# mc33775.net
KiCad netlist of a schematic drawn in Altium Designer
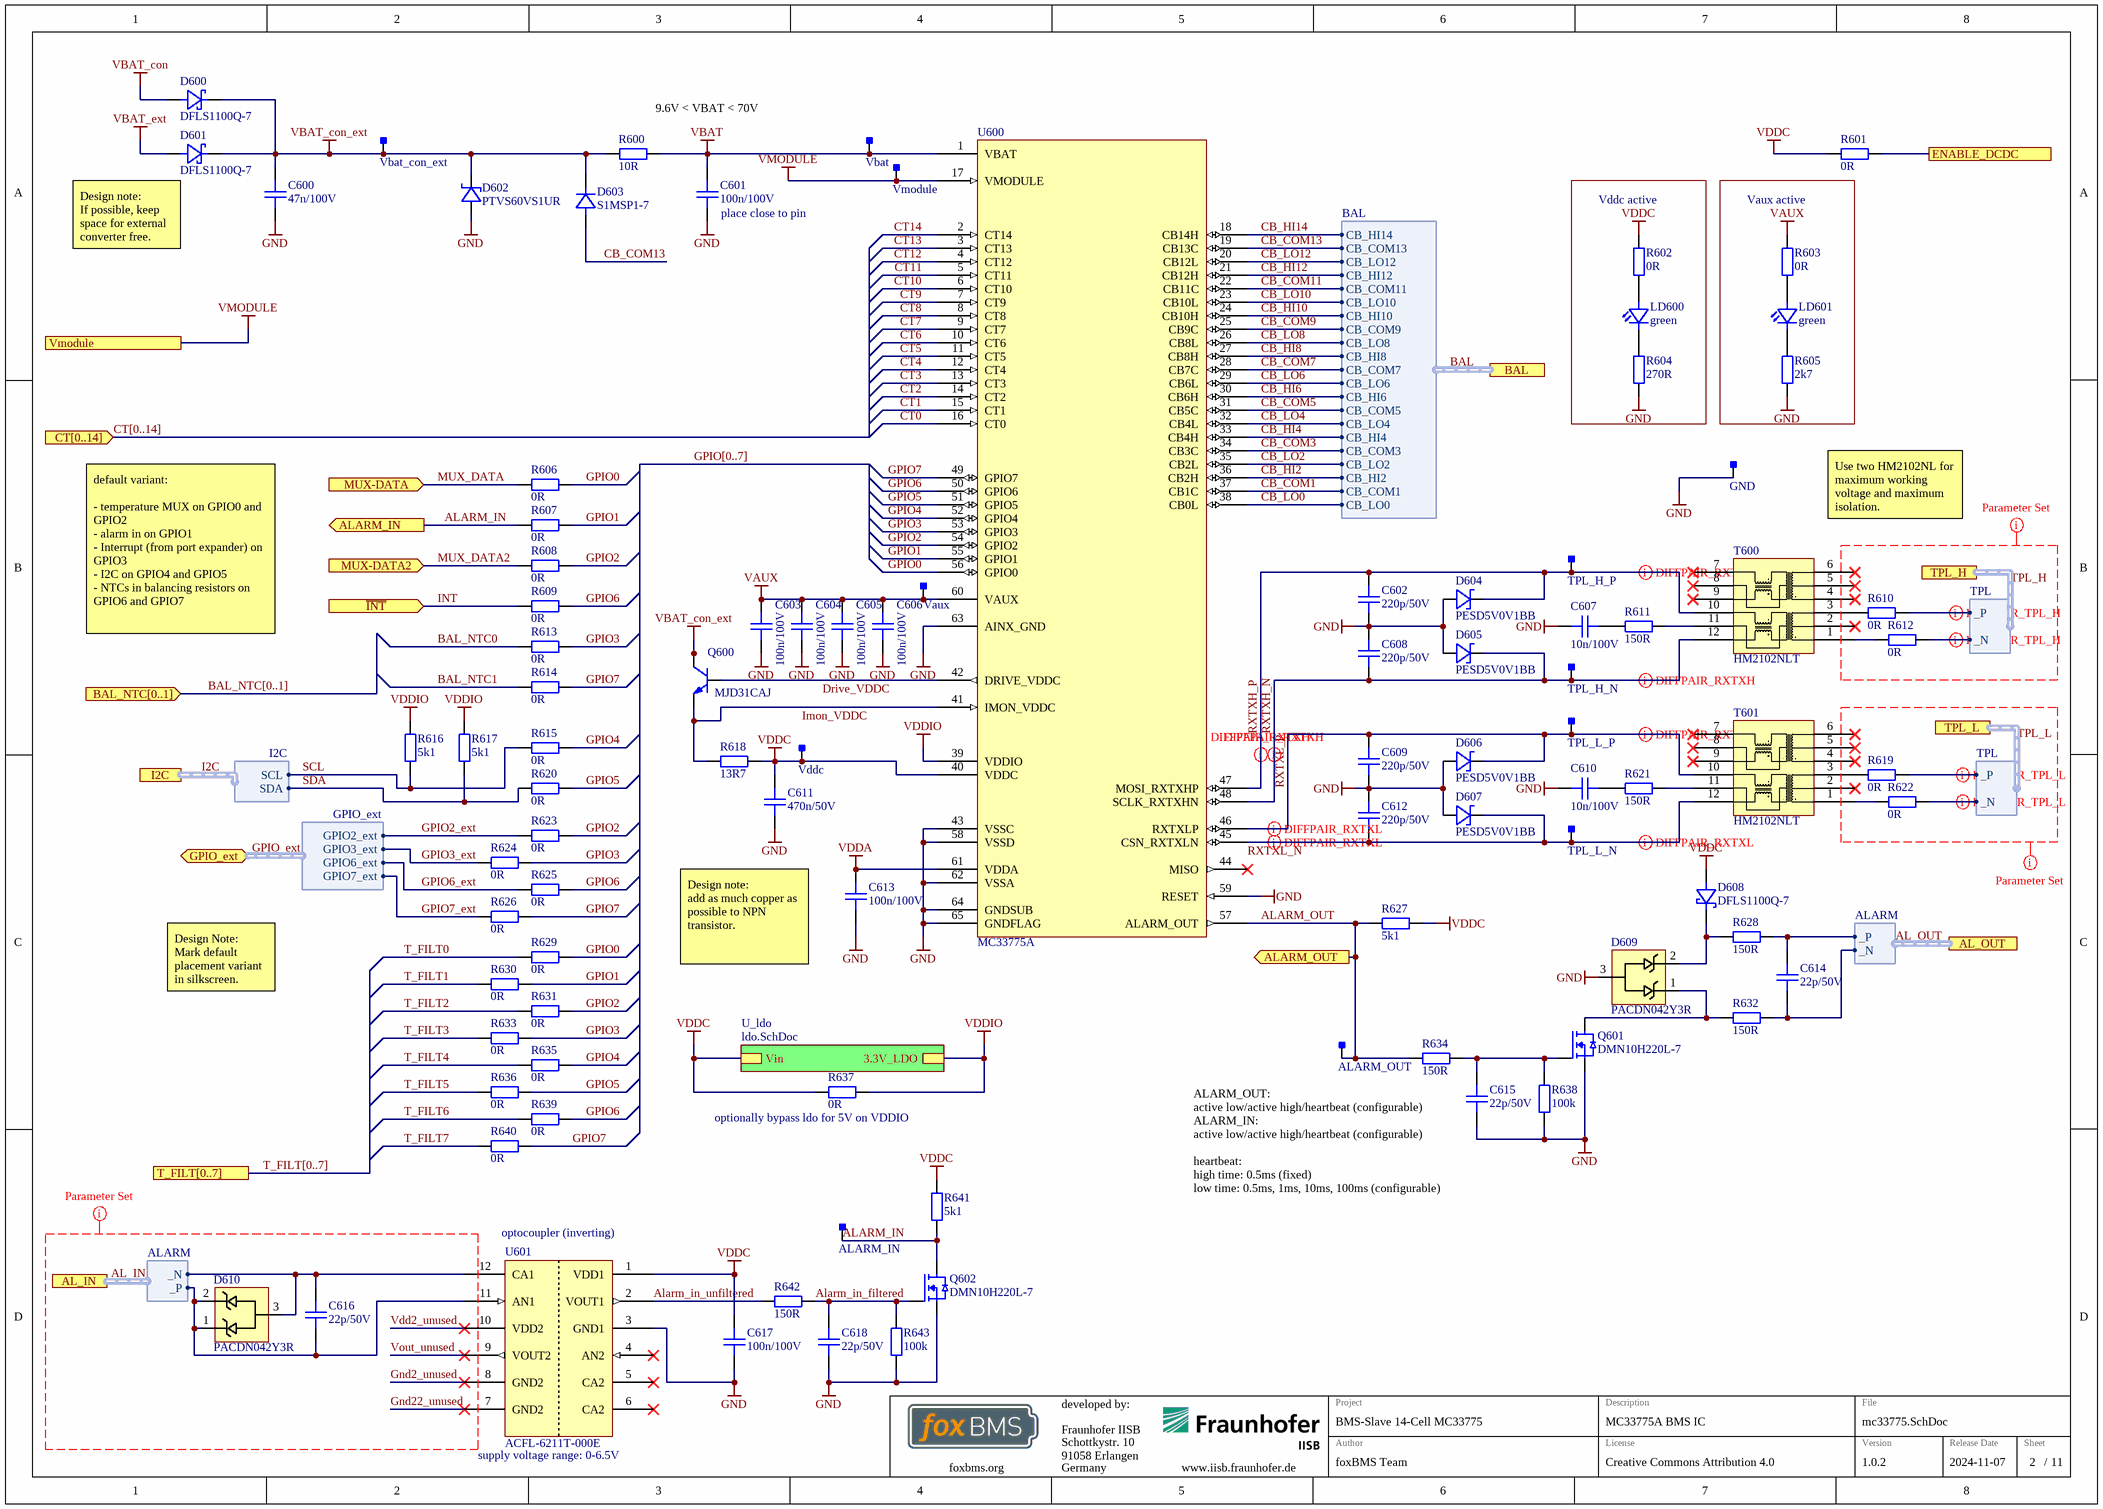
[diagram p0: mc33775.SchDoc]

(export (version "E")
  (design (tool "Eeschema 10.0.6"))
  (components
    (comp (ref "ALARM_IN")
      (value "Testpoint_Square")
      (footprint "Testpoint_S1")
      (description "Testpoint, square")
      (libsource (lib "OE750") (part "Testpoint_Square"))
    )
    (comp (ref "ALARM_OUT")
      (value "Testpoint_Square")
      (footprint "Testpoint_S1")
      (description "Testpoint, square")
      (libsource (lib "OE750") (part "Testpoint_Square"))
    )
    (comp (ref "C600")
      (value "47n/100V")
      (footprint "CAPC1608X08N")
      (description "MLCC")
      (fields (field (name "PART NUMBER") "gen_C_ceramic_47n_100V_X7R_0603"))
      (libsource (lib "OE750") (part "C"))
    )
    (comp (ref "C601")
      (value "100n/100V")
      (footprint "CAPC1608X08N")
      (description "MLCC")
      (fields (field (name "PART NUMBER") "gen_C_ceramic_100n_100V_X7R_0603"))
      (libsource (lib "OE750") (part "C"))
    )
    (comp (ref "C602")
      (value "220p/50V")
      (footprint "CAPC1608X08N")
      (description "MLCC")
      (fields (field (name "PART NUMBER") "gen_C_ceramic_220p_50V_C0G_0603"))
      (libsource (lib "OE750") (part "C"))
    )
    (comp (ref "C603")
      (value "100n/100V")
      (footprint "CAPC1608X08N")
      (description "MLCC")
      (fields (field (name "PART NUMBER") "gen_C_ceramic_100n_100V_X7R_0603"))
      (libsource (lib "OE750") (part "C"))
    )
    (comp (ref "C604")
      (value "100n/100V")
      (footprint "CAPC1608X08N")
      (description "MLCC")
      (fields (field (name "PART NUMBER") "gen_C_ceramic_100n_100V_X7R_0603"))
      (libsource (lib "OE750") (part "C"))
    )
    (comp (ref "C605")
      (value "100n/100V")
      (footprint "CAPC1608X08N")
      (description "MLCC")
      (fields (field (name "PART NUMBER") "gen_C_ceramic_100n_100V_X7R_0603"))
      (libsource (lib "OE750") (part "C"))
    )
    (comp (ref "C606")
      (value "100n/100V")
      (footprint "CAPC1608X08N")
      (description "MLCC")
      (fields (field (name "PART NUMBER") "gen_C_ceramic_100n_100V_X7R_0603"))
      (libsource (lib "OE750") (part "C"))
    )
    (comp (ref "C607")
      (value "10n/100V")
      (footprint "CAPC1608X08N")
      (description "MLCC")
      (fields (field (name "PART NUMBER") "gen_C_ceramic_10n_100V_X7R_0603"))
      (libsource (lib "OE750") (part "C"))
    )
    (comp (ref "C608")
      (value "220p/50V")
      (footprint "CAPC1608X08N")
      (description "MLCC")
      (fields (field (name "PART NUMBER") "gen_C_ceramic_220p_50V_C0G_0603"))
      (libsource (lib "OE750") (part "C"))
    )
    (comp (ref "C609")
      (value "220p/50V")
      (footprint "CAPC1608X08N")
      (description "MLCC")
      (fields (field (name "PART NUMBER") "gen_C_ceramic_220p_50V_C0G_0603"))
      (libsource (lib "OE750") (part "C"))
    )
    (comp (ref "C610")
      (value "10n/100V")
      (footprint "CAPC1608X08N")
      (description "MLCC")
      (fields (field (name "PART NUMBER") "gen_C_ceramic_10n_100V_X7R_0603"))
      (libsource (lib "OE750") (part "C"))
    )
    (comp (ref "C611")
      (value "470n/50V")
      (footprint "CAPC1608X08N")
      (description "MLCC")
      (fields (field (name "PART NUMBER") "gen_C_ceramic_470n_50V_X7R_0603"))
      (libsource (lib "OE750") (part "C"))
    )
    (comp (ref "C612")
      (value "220p/50V")
      (footprint "CAPC1608X08N")
      (description "MLCC")
      (fields (field (name "PART NUMBER") "gen_C_ceramic_220p_50V_C0G_0603"))
      (libsource (lib "OE750") (part "C"))
    )
    (comp (ref "C613")
      (value "100n/100V")
      (footprint "CAPC1608X08N")
      (description "MLCC")
      (fields (field (name "PART NUMBER") "gen_C_ceramic_100n_100V_X7R_0603"))
      (libsource (lib "OE750") (part "C"))
    )
    (comp (ref "C614")
      (value "22p/50V")
      (footprint "CAPC1005X06N")
      (description "MLCC")
      (fields (field (name "PART NUMBER") "gen_C_ceramic_22p_50V_C0G_0402") (field (name "TOLERANCE") "1%"))
      (libsource (lib "OE750") (part "C"))
    )
    (comp (ref "C615")
      (value "22p/50V")
      (footprint "CAPC1005X06N")
      (description "MLCC")
      (fields (field (name "PART NUMBER") "gen_C_ceramic_22p_50V_C0G_0402") (field (name "TOLERANCE") "1%"))
      (libsource (lib "OE750") (part "C"))
    )
    (comp (ref "C616")
      (value "22p/50V")
      (footprint "CAPC1005X06N")
      (description "MLCC")
      (fields (field (name "PART NUMBER") "gen_C_ceramic_22p_50V_C0G_0402") (field (name "TOLERANCE") "1%"))
      (libsource (lib "OE750") (part "C"))
    )
    (comp (ref "C617")
      (value "100n/100V")
      (footprint "CAPC1608X08N")
      (description "MLCC")
      (fields (field (name "PART NUMBER") "gen_C_ceramic_100n_100V_X7R_0603"))
      (libsource (lib "OE750") (part "C"))
    )
    (comp (ref "C618")
      (value "22p/50V")
      (footprint "CAPC1005X06N")
      (description "MLCC")
      (fields (field (name "PART NUMBER") "gen_C_ceramic_22p_50V_C0G_0402") (field (name "TOLERANCE") "1%"))
      (libsource (lib "OE750") (part "C"))
    )
    (comp (ref "D600")
      (value "DFLS1100Q-7")
      (footprint "PowerDI123")
      (description "Schottky Diode")
      (fields (field (name "MANUFACTURER") "Diodes Inc."))
      (libsource (lib "OE750") (part "D_Schottky"))
    )
    (comp (ref "D601")
      (value "DFLS1100Q-7")
      (footprint "PowerDI123")
      (description "Schottky Diode")
      (fields (field (name "MANUFACTURER") "Diodes Inc."))
      (libsource (lib "OE750") (part "D_Schottky"))
    )
    (comp (ref "D602")
      (value "PTVS60VS1UR")
      (footprint "NEXPERIA_PTVSxS1UR")
      (description "400W Transient Voltage Suppressor")
      (fields (field (name "MANUFACTURER") "Nexperia"))
      (libsource (lib "OE750") (part "D_TVS"))
    )
    (comp (ref "D603")
      (value "S1MSP1-7")
      (footprint "S1MSP1")
      (description "1.0A surface mount glass passivated rectifier")
      (fields (field (name "MANUFACTURER") "Diodes Inc."))
      (libsource (lib "OE750") (part "D"))
    )
    (comp (ref "D604")
      (value "PESD5V0V1BB")
      (footprint "SOD523_PESD_NEXPERIA")
      (description "Very low capacitance bidirectional ESD protection diode")
      (fields (field (name "MANUFACTURER") "Nexperia"))
      (libsource (lib "OE750") (part "D_TVS"))
    )
    (comp (ref "D605")
      (value "PESD5V0V1BB")
      (footprint "SOD523_PESD_NEXPERIA")
      (description "Very low capacitance bidirectional ESD protection diode")
      (fields (field (name "MANUFACTURER") "Nexperia"))
      (libsource (lib "OE750") (part "D_TVS"))
    )
    (comp (ref "D606")
      (value "PESD5V0V1BB")
      (footprint "SOD523_PESD_NEXPERIA")
      (description "Very low capacitance bidirectional ESD protection diode")
      (fields (field (name "MANUFACTURER") "Nexperia"))
      (libsource (lib "OE750") (part "D_TVS"))
    )
    (comp (ref "D607")
      (value "PESD5V0V1BB")
      (footprint "SOD523_PESD_NEXPERIA")
      (description "Very low capacitance bidirectional ESD protection diode")
      (fields (field (name "MANUFACTURER") "Nexperia"))
      (libsource (lib "OE750") (part "D_TVS"))
    )
    (comp (ref "D608")
      (value "DFLS1100Q-7")
      (footprint "PowerDI123")
      (description "Schottky Diode")
      (fields (field (name "MANUFACTURER") "Diodes Inc."))
      (libsource (lib "OE750") (part "D_Schottky"))
    )
    (comp (ref "D609")
      (value "PACDN042Y3R")
      (footprint "ON-SEMI-SOT-23-3-CASE-318-08")
      (description "ESD-Schutzbaustein")
      (fields (field (name "MANUFACTURER") "ON Semiconductor"))
      (libsource (lib "") (part "PACDN042_1"))
    )
    (comp (ref "D610")
      (value "PACDN042Y3R")
      (footprint "ON-SEMI-SOT-23-3-CASE-318-08")
      (description "ESD-Schutzbaustein")
      (fields (field (name "MANUFACTURER") "ON Semiconductor"))
      (libsource (lib "OE750") (part "PACDN042"))
    )
    (comp (ref "GND")
      (value "Testpoint_Square")
      (footprint "Testpoint_S1")
      (description "Testpoint, square")
      (libsource (lib "OE750") (part "Testpoint_Square"))
    )
    (comp (ref "LD600")
      (value "green")
      (footprint "LEDC1608X07N")
      (description "TLMG1100-GS08")
      (fields (field (name "PART NUMBER") "LED_0603_green_AECQ") (field (name "MANUFACTURER") "Vishay"))
      (libsource (lib "OE750") (part "D_LED"))
    )
    (comp (ref "LD601")
      (value "green")
      (footprint "LEDC1608X07N")
      (description "TLMG1100-GS08")
      (fields (field (name "PART NUMBER") "LED_0603_green_AECQ") (field (name "MANUFACTURER") "Vishay"))
      (libsource (lib "OE750") (part "D_LED"))
    )
    (comp (ref "Q600")
      (value "MJD31CAJ")
      (footprint "NEXPERIA_DPAK_SOT428C")
      (description "100V, 3A NPN high power bipolar transistor")
      (fields (field (name "MANUFACTURER") "Nexperia"))
      (libsource (lib "OE750") (part "NPN_4_PIN"))
    )
    (comp (ref "Q601")
      (value "DMN10H220L-7")
      (footprint "SOT95P237X110-3N")
      (description "MOSFET-Transistor, n-Kanal, 1.6 A, 100 V, 0.250 ohm")
      (fields (field (name "MANUFACTURER") "Diodes"))
      (libsource (lib "OE750") (part "NMOS"))
    )
    (comp (ref "Q602")
      (value "DMN10H220L-7")
      (footprint "SOT95P237X110-3N")
      (description "MOSFET-Transistor, n-Kanal, 1.6 A, 100 V, 0.250 ohm")
      (fields (field (name "MANUFACTURER") "Diodes"))
      (libsource (lib "OE750") (part "NMOS"))
    )
    (comp (ref "R600")
      (value "10R")
      (footprint "RESC2012X05N")
      (description "SMD Resistor 10R 0805")
      (fields (field (name "PART NUMBER") "gen_R_10R_0805") (field (name "TOLERANCE") "1%"))
      (libsource (lib "OE750") (part "R"))
    )
    (comp (ref "R601")
      (value "0R")
      (footprint "RESC1608X05N")
      (description "SMD Resistor 0R 0603")
      (fields (field (name "PART NUMBER") "gen_R_0R_0603") (field (name "POWER") "0.1W"))
      (libsource (lib "OE750") (part "R"))
    )
    (comp (ref "R602")
      (value "0R")
      (footprint "RESC1608X05N")
      (description "SMD Resistor 0R 0603")
      (fields (field (name "PART NUMBER") "gen_R_0R_0603") (field (name "POWER") "0.1W"))
      (libsource (lib "OE750") (part "R"))
    )
    (comp (ref "R603")
      (value "0R")
      (footprint "RESC1608X05N")
      (description "SMD Resistor 0R 0603")
      (fields (field (name "PART NUMBER") "gen_R_0R_0603") (field (name "POWER") "0.1W"))
      (libsource (lib "OE750") (part "R"))
    )
    (comp (ref "R604")
      (value "270R")
      (footprint "RESC1608X05N")
      (description "SMD Resistor 270R 0603")
      (fields (field (name "PART NUMBER") "gen_R_270R_0603") (field (name "TOLERANCE") "1%"))
      (libsource (lib "OE750") (part "R"))
    )
    (comp (ref "R605")
      (value "2k7")
      (footprint "RESC1608X05N")
      (description "SMD Resistor 2k7 0603")
      (fields (field (name "PART NUMBER") "gen_R_2k7_0603") (field (name "TOLERANCE") "1%"))
      (libsource (lib "OE750") (part "R"))
    )
    (comp (ref "R606")
      (value "0R")
      (footprint "RESC1608X05N")
      (description "SMD Resistor 0R 0603")
      (fields (field (name "PART NUMBER") "gen_R_0R_0603") (field (name "POWER") "0.1W"))
      (libsource (lib "OE750") (part "R"))
    )
    (comp (ref "R607")
      (value "0R")
      (footprint "RESC1608X05N")
      (description "SMD Resistor 0R 0603")
      (fields (field (name "PART NUMBER") "gen_R_0R_0603") (field (name "POWER") "0.1W"))
      (libsource (lib "OE750") (part "R"))
    )
    (comp (ref "R608")
      (value "0R")
      (footprint "RESC1608X05N")
      (description "SMD Resistor 0R 0603")
      (fields (field (name "PART NUMBER") "gen_R_0R_0603") (field (name "POWER") "0.1W"))
      (libsource (lib "OE750") (part "R"))
    )
    (comp (ref "R609")
      (value "0R")
      (footprint "RESC1608X05N")
      (description "SMD Resistor 0R 0603")
      (fields (field (name "PART NUMBER") "gen_R_0R_0603") (field (name "POWER") "0.1W"))
      (libsource (lib "OE750") (part "R"))
    )
    (comp (ref "R610")
      (value "0R")
      (footprint "RESC1608X05N")
      (description "SMD Resistor 0R 0603")
      (fields (field (name "PART NUMBER") "gen_R_0R_0603") (field (name "POWER") "0.1W"))
      (libsource (lib "OE750") (part "R"))
    )
    (comp (ref "R611")
      (value "150R")
      (footprint "RESC1608X05N")
      (description "SMD Resistor 150R 0603")
      (fields (field (name "PART NUMBER") "gen_R_150R_0603") (field (name "TOLERANCE") "1%"))
      (libsource (lib "OE750") (part "R"))
    )
    (comp (ref "R612")
      (value "0R")
      (footprint "RESC1608X05N")
      (description "SMD Resistor 0R 0603")
      (fields (field (name "PART NUMBER") "gen_R_0R_0603") (field (name "POWER") "0.1W"))
      (libsource (lib "OE750") (part "R"))
    )
    (comp (ref "R613")
      (value "0R")
      (footprint "RESC1608X05N")
      (description "SMD Resistor 0R 0603")
      (fields (field (name "PART NUMBER") "gen_R_0R_0603") (field (name "POWER") "0.1W"))
      (libsource (lib "OE750") (part "R"))
    )
    (comp (ref "R614")
      (value "0R")
      (footprint "RESC1608X05N")
      (description "SMD Resistor 0R 0603")
      (fields (field (name "PART NUMBER") "gen_R_0R_0603") (field (name "POWER") "0.1W"))
      (libsource (lib "OE750") (part "R"))
    )
    (comp (ref "R615")
      (value "0R")
      (footprint "RESC1608X05N")
      (description "SMD Resistor 0R 0603")
      (fields (field (name "PART NUMBER") "gen_R_0R_0603") (field (name "POWER") "0.1W"))
      (libsource (lib "OE750") (part "R"))
    )
    (comp (ref "R616")
      (value "5k1")
      (footprint "RESC1608X05N")
      (description "SMD Resistor 5k1 0603")
      (fields (field (name "PART NUMBER") "gen_R_5k1_0603") (field (name "TOLERANCE") "5%"))
      (libsource (lib "OE750") (part "R"))
    )
    (comp (ref "R617")
      (value "5k1")
      (footprint "RESC1608X05N")
      (description "SMD Resistor 5k1 0603")
      (fields (field (name "PART NUMBER") "gen_R_5k1_0603") (field (name "TOLERANCE") "5%"))
      (libsource (lib "OE750") (part "R"))
    )
    (comp (ref "R618")
      (value "13R7")
      (footprint "RESC1608X05N")
      (description "SMD Resistor 13R7 0603")
      (fields (field (name "PART NUMBER") "gen_R_13R7_0603") (field (name "TOLERANCE") "1%"))
      (libsource (lib "OE750") (part "R"))
    )
    (comp (ref "R619")
      (value "0R")
      (footprint "RESC1608X05N")
      (description "SMD Resistor 0R 0603")
      (fields (field (name "PART NUMBER") "gen_R_0R_0603") (field (name "POWER") "0.1W"))
      (libsource (lib "OE750") (part "R"))
    )
    (comp (ref "R620")
      (value "0R")
      (footprint "RESC1608X05N")
      (description "SMD Resistor 0R 0603")
      (fields (field (name "PART NUMBER") "gen_R_0R_0603") (field (name "POWER") "0.1W"))
      (libsource (lib "OE750") (part "R"))
    )
    (comp (ref "R621")
      (value "150R")
      (footprint "RESC1608X05N")
      (description "SMD Resistor 150R 0603")
      (fields (field (name "PART NUMBER") "gen_R_150R_0603") (field (name "TOLERANCE") "1%"))
      (libsource (lib "OE750") (part "R"))
    )
    (comp (ref "R622")
      (value "0R")
      (footprint "RESC1608X05N")
      (description "SMD Resistor 0R 0603")
      (fields (field (name "PART NUMBER") "gen_R_0R_0603") (field (name "POWER") "0.1W"))
      (libsource (lib "OE750") (part "R"))
    )
    (comp (ref "R623")
      (value "0R")
      (footprint "RESC1608X05N")
      (description "SMD Resistor 0R 0603")
      (fields (field (name "PART NUMBER") "gen_R_0R_0603") (field (name "POWER") "0.1W"))
      (libsource (lib "OE750") (part "R"))
    )
    (comp (ref "R624")
      (value "0R")
      (footprint "RESC1608X05N")
      (description "SMD Resistor 0R 0603")
      (fields (field (name "PART NUMBER") "gen_R_0R_0603") (field (name "POWER") "0.1W"))
      (libsource (lib "OE750") (part "R"))
    )
    (comp (ref "R625")
      (value "0R")
      (footprint "RESC1608X05N")
      (description "SMD Resistor 0R 0603")
      (fields (field (name "PART NUMBER") "gen_R_0R_0603") (field (name "POWER") "0.1W"))
      (libsource (lib "OE750") (part "R"))
    )
    (comp (ref "R626")
      (value "0R")
      (footprint "RESC1608X05N")
      (description "SMD Resistor 0R 0603")
      (fields (field (name "PART NUMBER") "gen_R_0R_0603") (field (name "POWER") "0.1W"))
      (libsource (lib "OE750") (part "R"))
    )
    (comp (ref "R627")
      (value "5k1")
      (footprint "RESC1608X05N")
      (description "SMD Resistor 5k1 0603")
      (fields (field (name "PART NUMBER") "gen_R_5k1_0603") (field (name "TOLERANCE") "5%"))
      (libsource (lib "OE750") (part "R"))
    )
    (comp (ref "R628")
      (value "150R")
      (footprint "RESC1608X05N")
      (description "SMD Resistor 150R 0603")
      (fields (field (name "PART NUMBER") "gen_R_150R_0603") (field (name "TOLERANCE") "1%"))
      (libsource (lib "OE750") (part "R"))
    )
    (comp (ref "R629")
      (value "0R")
      (footprint "RESC1608X05N")
      (description "SMD Resistor 0R 0603")
      (fields (field (name "PART NUMBER") "gen_R_0R_0603") (field (name "POWER") "0.1W"))
      (libsource (lib "OE750") (part "R"))
    )
    (comp (ref "R630")
      (value "0R")
      (footprint "RESC1608X05N")
      (description "SMD Resistor 0R 0603")
      (fields (field (name "PART NUMBER") "gen_R_0R_0603") (field (name "POWER") "0.1W"))
      (libsource (lib "OE750") (part "R"))
    )
    (comp (ref "R631")
      (value "0R")
      (footprint "RESC1608X05N")
      (description "SMD Resistor 0R 0603")
      (fields (field (name "PART NUMBER") "gen_R_0R_0603") (field (name "POWER") "0.1W"))
      (libsource (lib "OE750") (part "R"))
    )
    (comp (ref "R632")
      (value "150R")
      (footprint "RESC1608X05N")
      (description "SMD Resistor 150R 0603")
      (fields (field (name "PART NUMBER") "gen_R_150R_0603") (field (name "TOLERANCE") "1%"))
      (libsource (lib "OE750") (part "R"))
    )
    (comp (ref "R633")
      (value "0R")
      (footprint "RESC1608X05N")
      (description "SMD Resistor 0R 0603")
      (fields (field (name "PART NUMBER") "gen_R_0R_0603") (field (name "POWER") "0.1W"))
      (libsource (lib "OE750") (part "R"))
    )
    (comp (ref "R634")
      (value "150R")
      (footprint "RESC1608X05N")
      (description "SMD Resistor 150R 0603")
      (fields (field (name "PART NUMBER") "gen_R_150R_0603") (field (name "TOLERANCE") "1%"))
      (libsource (lib "OE750") (part "R"))
    )
    (comp (ref "R635")
      (value "0R")
      (footprint "RESC1608X05N")
      (description "SMD Resistor 0R 0603")
      (fields (field (name "PART NUMBER") "gen_R_0R_0603") (field (name "POWER") "0.1W"))
      (libsource (lib "OE750") (part "R"))
    )
    (comp (ref "R636")
      (value "0R")
      (footprint "RESC1608X05N")
      (description "SMD Resistor 0R 0603")
      (fields (field (name "PART NUMBER") "gen_R_0R_0603") (field (name "POWER") "0.1W"))
      (libsource (lib "OE750") (part "R"))
    )
    (comp (ref "R637")
      (value "0R")
      (footprint "RESC1608X05N")
      (description "SMD Resistor 0R 0603")
      (fields (field (name "PART NUMBER") "gen_R_0R_0603") (field (name "POWER") "0.1W"))
      (libsource (lib "OE750") (part "R"))
    )
    (comp (ref "R638")
      (value "100k")
      (footprint "RESC1608X05N")
      (description "SMD Resistor 100k 0603")
      (fields (field (name "PART NUMBER") "gen_R_100k_0603") (field (name "TOLERANCE") "1%"))
      (libsource (lib "OE750") (part "R"))
    )
    (comp (ref "R639")
      (value "0R")
      (footprint "RESC1608X05N")
      (description "SMD Resistor 0R 0603")
      (fields (field (name "PART NUMBER") "gen_R_0R_0603") (field (name "POWER") "0.1W"))
      (libsource (lib "OE750") (part "R"))
    )
    (comp (ref "R640")
      (value "0R")
      (footprint "RESC1608X05N")
      (description "SMD Resistor 0R 0603")
      (fields (field (name "PART NUMBER") "gen_R_0R_0603") (field (name "POWER") "0.1W"))
      (libsource (lib "OE750") (part "R"))
    )
    (comp (ref "R641")
      (value "5k1")
      (footprint "RESC1608X05N")
      (description "SMD Resistor 5k1 0603")
      (fields (field (name "PART NUMBER") "gen_R_5k1_0603") (field (name "TOLERANCE") "5%"))
      (libsource (lib "OE750") (part "R"))
    )
    (comp (ref "R642")
      (value "150R")
      (footprint "RESC1608X05N")
      (description "SMD Resistor 150R 0603")
      (fields (field (name "PART NUMBER") "gen_R_150R_0603") (field (name "TOLERANCE") "1%"))
      (libsource (lib "OE750") (part "R"))
    )
    (comp (ref "R643")
      (value "100k")
      (footprint "RESC1608X05N")
      (description "SMD Resistor 100k 0603")
      (fields (field (name "PART NUMBER") "gen_R_100k_0603") (field (name "TOLERANCE") "1%"))
      (libsource (lib "OE750") (part "R"))
    )
    (comp (ref "T600")
      (value "HM2102NLT")
      (footprint "HM2102NL")
      (description "Pulse HM2102NLT BMS Transformer")
      (fields (field (name "MANUFACTURER") "Pulse"))
      (libsource (lib "OE750") (part "HM2102NL"))
    )
    (comp (ref "T601")
      (value "HM2102NLT")
      (footprint "HM2102NL")
      (description "Pulse HM2102NLT BMS Transformer")
      (fields (field (name "MANUFACTURER") "Pulse"))
      (libsource (lib "OE750") (part "HM2102NL"))
    )
    (comp (ref "TPL_H_N")
      (value "Testpoint_Square")
      (footprint "Testpoint_S1")
      (description "Testpoint, square")
      (libsource (lib "OE750") (part "Testpoint_Square"))
    )
    (comp (ref "TPL_H_P")
      (value "Testpoint_Square")
      (footprint "Testpoint_S1")
      (description "Testpoint, square")
      (libsource (lib "OE750") (part "Testpoint_Square"))
    )
    (comp (ref "TPL_L_N")
      (value "Testpoint_Square")
      (footprint "Testpoint_S1")
      (description "Testpoint, square")
      (libsource (lib "OE750") (part "Testpoint_Square"))
    )
    (comp (ref "TPL_L_P")
      (value "Testpoint_Square")
      (footprint "Testpoint_S1")
      (description "Testpoint, square")
      (libsource (lib "OE750") (part "Testpoint_Square"))
    )
    (comp (ref "U600")
      (value "MC33775A")
      (footprint "NXP_SOT1510-2")
      (description "14 Cells Battery Cell Controller IC")
      (fields (field (name "MANUFACTURER") "NXP"))
      (libsource (lib "OE750") (part "MC33775"))
    )
    (comp (ref "U601")
      (value "ACFL-6211T-000E")
      (footprint "Broadcom_ACFL-6211T")
      (description "15MBd Dual-channel Bi-directional Optocoupler")
      (fields (field (name "MANUFACTURER") "Broadcom"))
      (libsource (lib "OE750") (part "ACFL-6211T"))
    )
    (comp (ref "Vaux")
      (value "Testpoint_Square")
      (footprint "Testpoint_S1")
      (description "Testpoint, square")
      (libsource (lib "OE750") (part "Testpoint_Square"))
    )
    (comp (ref "Vbat")
      (value "Testpoint_Square")
      (footprint "Testpoint_S1")
      (description "Testpoint, square")
      (libsource (lib "OE750") (part "Testpoint_Square"))
    )
    (comp (ref "Vbat_con_ext")
      (value "Testpoint_Square")
      (footprint "Testpoint_S1")
      (description "Testpoint, square")
      (libsource (lib "OE750") (part "Testpoint_Square"))
    )
    (comp (ref "Vddc")
      (value "Testpoint_Square")
      (footprint "Testpoint_S1")
      (description "Testpoint, square")
      (libsource (lib "OE750") (part "Testpoint_Square"))
    )
    (comp (ref "Vmodule")
      (value "Testpoint_Square")
      (footprint "Testpoint_S1")
      (description "Testpoint, square")
      (libsource (lib "OE750") (part "Testpoint_Square"))
    )
  )
  (nets
    (net (code "8") (name "/ALARM_IN") (class "Default")
      (node (ref "ALARM_IN") (pin "1") (pinfunction "1_1") (pintype "passive"))
      (node (ref "Q602") (pin "D") (pinfunction "D_D") (pintype "passive"))
      (node (ref "R607") (pin "1") (pinfunction "1_1") (pintype "passive"))
      (node (ref "R641") (pin "2") (pinfunction "2_2") (pintype "passive"))
    )
    (net (code "9") (name "/ALARM_OUT") (class "Default")
      (node (ref "ALARM_OUT") (pin "1") (pinfunction "1_1") (pintype "passive"))
      (node (ref "R627") (pin "2") (pinfunction "2_2") (pintype "passive"))
      (node (ref "R634") (pin "1") (pinfunction "1_1") (pintype "passive"))
      (node (ref "U600") (pin "57") (pinfunction "ALARM_OUT_57") (pintype "output"))
    )
    (net (code "12") (name "/Alarm_in_filtered") (class "Default")
      (node (ref "C618") (pin "2") (pinfunction "2_2") (pintype "passive"))
      (node (ref "Q602") (pin "G") (pinfunction "G_G") (pintype "passive"))
      (node (ref "R642") (pin "2") (pinfunction "2_2") (pintype "passive"))
      (node (ref "R643") (pin "1") (pinfunction "1_1") (pintype "passive"))
    )
    (net (code "13") (name "/Alarm_in_unfiltered") (class "Default")
      (node (ref "R642") (pin "1") (pinfunction "1_1") (pintype "passive"))
      (node (ref "U601") (pin "2") (pinfunction "VOUT1_2") (pintype "output"))
    )
    (net (code "14") (name "/BAL_NTC0") (class "Default")
      (node (ref "R613") (pin "1") (pinfunction "1_1") (pintype "passive"))
    )
    (net (code "15") (name "/BAL_NTC1") (class "Default")
      (node (ref "R614") (pin "1") (pinfunction "1_1") (pintype "passive"))
    )
    (net (code "18") (name "/CB_COM1") (class "Default")
      (node (ref "U600") (pin "37") (pinfunction "CB1C_37") (pintype "bidirectional"))
    )
    (net (code "19") (name "/CB_COM3") (class "Default")
      (node (ref "U600") (pin "34") (pinfunction "CB3C_34") (pintype "bidirectional"))
    )
    (net (code "20") (name "/CB_COM5") (class "Default")
      (node (ref "U600") (pin "31") (pinfunction "CB5C_31") (pintype "bidirectional"))
    )
    (net (code "21") (name "/CB_COM7") (class "Default")
      (node (ref "U600") (pin "28") (pinfunction "CB7C_28") (pintype "bidirectional"))
    )
    (net (code "22") (name "/CB_COM9") (class "Default")
      (node (ref "U600") (pin "25") (pinfunction "CB9C_25") (pintype "bidirectional"))
    )
    (net (code "23") (name "/CB_COM11") (class "Default")
      (node (ref "U600") (pin "22") (pinfunction "CB11C_22") (pintype "bidirectional"))
    )
    (net (code "24") (name "/CB_COM13") (class "Default")
      (node (ref "D603") (pin "2") (pinfunction "A_2") (pintype "passive"))
      (node (ref "U600") (pin "19") (pinfunction "CB13C_19") (pintype "bidirectional"))
    )
    (net (code "25") (name "/CB_HI2") (class "Default")
      (node (ref "U600") (pin "36") (pinfunction "CB2H_36") (pintype "bidirectional"))
    )
    (net (code "26") (name "/CB_HI4") (class "Default")
      (node (ref "U600") (pin "33") (pinfunction "CB4H_33") (pintype "bidirectional"))
    )
    (net (code "27") (name "/CB_HI6") (class "Default")
      (node (ref "U600") (pin "30") (pinfunction "CB6H_30") (pintype "bidirectional"))
    )
    (net (code "28") (name "/CB_HI8") (class "Default")
      (node (ref "U600") (pin "27") (pinfunction "CB8H_27") (pintype "bidirectional"))
    )
    (net (code "29") (name "/CB_HI10") (class "Default")
      (node (ref "U600") (pin "24") (pinfunction "CB10H_24") (pintype "bidirectional"))
    )
    (net (code "30") (name "/CB_HI12") (class "Default")
      (node (ref "U600") (pin "21") (pinfunction "CB12H_21") (pintype "bidirectional"))
    )
    (net (code "31") (name "/CB_HI14") (class "Default")
      (node (ref "U600") (pin "18") (pinfunction "CB14H_18") (pintype "bidirectional"))
    )
    (net (code "32") (name "/CB_LO0") (class "Default")
      (node (ref "U600") (pin "38") (pinfunction "CB0L_38") (pintype "bidirectional"))
    )
    (net (code "33") (name "/CB_LO2") (class "Default")
      (node (ref "U600") (pin "35") (pinfunction "CB2L_35") (pintype "bidirectional"))
    )
    (net (code "34") (name "/CB_LO4") (class "Default")
      (node (ref "U600") (pin "32") (pinfunction "CB4L_32") (pintype "bidirectional"))
    )
    (net (code "35") (name "/CB_LO6") (class "Default")
      (node (ref "U600") (pin "29") (pinfunction "CB6L_29") (pintype "bidirectional"))
    )
    (net (code "36") (name "/CB_LO8") (class "Default")
      (node (ref "U600") (pin "26") (pinfunction "CB8L_26") (pintype "bidirectional"))
    )
    (net (code "37") (name "/CB_LO10") (class "Default")
      (node (ref "U600") (pin "23") (pinfunction "CB10L_23") (pintype "bidirectional"))
    )
    (net (code "38") (name "/CB_LO12") (class "Default")
      (node (ref "U600") (pin "20") (pinfunction "CB12L_20") (pintype "bidirectional"))
    )
    (net (code "39") (name "/CT0") (class "Default")
      (node (ref "U600") (pin "16") (pinfunction "CT0_16") (pintype "input"))
    )
    (net (code "40") (name "/CT1") (class "Default")
      (node (ref "U600") (pin "15") (pinfunction "CT1_15") (pintype "input"))
    )
    (net (code "41") (name "/CT2") (class "Default")
      (node (ref "U600") (pin "14") (pinfunction "CT2_14") (pintype "input"))
    )
    (net (code "42") (name "/CT3") (class "Default")
      (node (ref "U600") (pin "13") (pinfunction "CT3_13") (pintype "input"))
    )
    (net (code "43") (name "/CT4") (class "Default")
      (node (ref "U600") (pin "12") (pinfunction "CT4_12") (pintype "input"))
    )
    (net (code "44") (name "/CT5") (class "Default")
      (node (ref "U600") (pin "11") (pinfunction "CT5_11") (pintype "input"))
    )
    (net (code "45") (name "/CT6") (class "Default")
      (node (ref "U600") (pin "10") (pinfunction "CT6_10") (pintype "input"))
    )
    (net (code "46") (name "/CT7") (class "Default")
      (node (ref "U600") (pin "9") (pinfunction "CT7_9") (pintype "input"))
    )
    (net (code "47") (name "/CT8") (class "Default")
      (node (ref "U600") (pin "8") (pinfunction "CT8_8") (pintype "input"))
    )
    (net (code "48") (name "/CT9") (class "Default")
      (node (ref "U600") (pin "7") (pinfunction "CT9_7") (pintype "input"))
    )
    (net (code "49") (name "/CT10") (class "Default")
      (node (ref "U600") (pin "6") (pinfunction "CT10_6") (pintype "input"))
    )
    (net (code "50") (name "/CT11") (class "Default")
      (node (ref "U600") (pin "5") (pinfunction "CT11_5") (pintype "input"))
    )
    (net (code "51") (name "/CT12") (class "Default")
      (node (ref "U600") (pin "4") (pinfunction "CT12_4") (pintype "input"))
    )
    (net (code "52") (name "/CT13") (class "Default")
      (node (ref "U600") (pin "3") (pinfunction "CT13_3") (pintype "input"))
    )
    (net (code "53") (name "/CT14") (class "Default")
      (node (ref "U600") (pin "2") (pinfunction "CT14_2") (pintype "input"))
    )
    (net (code "55") (name "/Drive_VDDC") (class "Default")
      (node (ref "Q600") (pin "1") (pinfunction "B_1") (pintype "passive"))
      (node (ref "U600") (pin "42") (pinfunction "DRIVE_VDDC_42") (pintype "output"))
    )
    (net (code "56") (name "/ENABLE_DCDC") (class "Default")
      (node (ref "R601") (pin "2") (pinfunction "2_2") (pintype "passive"))
    )
    (net (code "57") (name "/GPIO0") (class "Default")
      (node (ref "R606") (pin "2") (pinfunction "2_2") (pintype "passive"))
      (node (ref "R629") (pin "2") (pinfunction "2_2") (pintype "passive"))
      (node (ref "U600") (pin "56") (pinfunction "GPIO0_56") (pintype "bidirectional"))
    )
    (net (code "58") (name "/GPIO1") (class "Default")
      (node (ref "R607") (pin "2") (pinfunction "2_2") (pintype "passive"))
      (node (ref "R630") (pin "2") (pinfunction "2_2") (pintype "passive"))
      (node (ref "U600") (pin "55") (pinfunction "GPIO1_55") (pintype "bidirectional"))
    )
    (net (code "59") (name "/GPIO2") (class "Default")
      (node (ref "R608") (pin "2") (pinfunction "2_2") (pintype "passive"))
      (node (ref "R623") (pin "2") (pinfunction "2_2") (pintype "passive"))
      (node (ref "R631") (pin "2") (pinfunction "2_2") (pintype "passive"))
      (node (ref "U600") (pin "54") (pinfunction "GPIO2_54") (pintype "bidirectional"))
    )
    (net (code "60") (name "/GPIO2_ext") (class "Default")
      (node (ref "R623") (pin "1") (pinfunction "1_1") (pintype "passive"))
    )
    (net (code "61") (name "/GPIO3") (class "Default")
      (node (ref "R613") (pin "2") (pinfunction "2_2") (pintype "passive"))
      (node (ref "R624") (pin "2") (pinfunction "2_2") (pintype "passive"))
      (node (ref "R633") (pin "2") (pinfunction "2_2") (pintype "passive"))
      (node (ref "U600") (pin "53") (pinfunction "GPIO3_53") (pintype "bidirectional"))
    )
    (net (code "62") (name "/GPIO3_ext") (class "Default")
      (node (ref "R624") (pin "1") (pinfunction "1_1") (pintype "passive"))
    )
    (net (code "63") (name "/GPIO4") (class "Default")
      (node (ref "R615") (pin "2") (pinfunction "2_2") (pintype "passive"))
      (node (ref "R635") (pin "2") (pinfunction "2_2") (pintype "passive"))
      (node (ref "U600") (pin "52") (pinfunction "GPIO4_52") (pintype "bidirectional"))
    )
    (net (code "64") (name "/GPIO5") (class "Default")
      (node (ref "R620") (pin "2") (pinfunction "2_2") (pintype "passive"))
      (node (ref "R636") (pin "2") (pinfunction "2_2") (pintype "passive"))
      (node (ref "U600") (pin "51") (pinfunction "GPIO5_51") (pintype "bidirectional"))
    )
    (net (code "65") (name "/GPIO6") (class "Default")
      (node (ref "R609") (pin "2") (pinfunction "2_2") (pintype "passive"))
      (node (ref "R625") (pin "2") (pinfunction "2_2") (pintype "passive"))
      (node (ref "R639") (pin "2") (pinfunction "2_2") (pintype "passive"))
      (node (ref "U600") (pin "50") (pinfunction "GPIO6_50") (pintype "bidirectional"))
    )
    (net (code "66") (name "/GPIO6_ext") (class "Default")
      (node (ref "R625") (pin "1") (pinfunction "1_1") (pintype "passive"))
    )
    (net (code "67") (name "/GPIO7") (class "Default")
      (node (ref "R614") (pin "2") (pinfunction "2_2") (pintype "passive"))
      (node (ref "R626") (pin "2") (pinfunction "2_2") (pintype "passive"))
      (node (ref "R640") (pin "2") (pinfunction "2_2") (pintype "passive"))
      (node (ref "U600") (pin "49") (pinfunction "GPIO7_49") (pintype "bidirectional"))
    )
    (net (code "68") (name "/GPIO7_ext") (class "Default")
      (node (ref "R626") (pin "1") (pinfunction "1_1") (pintype "passive"))
    )
    (net (code "71") (name "/Gnd2_unused") (class "Default")
      (node (ref "U601") (pin "8") (pinfunction "GND2_8") (pintype "power_in+no_connect"))
    )
    (net (code "72") (name "/Gnd22_unused") (class "Default")
      (node (ref "U601") (pin "7") (pinfunction "GND2_7") (pintype "power_in+no_connect"))
    )
    (net (code "74") (name "/INT") (class "Default")
      (node (ref "R609") (pin "1") (pinfunction "1_1") (pintype "passive"))
    )
    (net (code "75") (name "/Imon_VDDC") (class "Default")
      (node (ref "Q600") (pin "3") (pinfunction "E_3") (pintype "passive"))
      (node (ref "R618") (pin "2") (pinfunction "2_2") (pintype "passive"))
      (node (ref "U600") (pin "41") (pinfunction "IMON_VDDC_41") (pintype "input"))
    )
    (net (code "76") (name "/MUX_DATA") (class "Default")
      (node (ref "R606") (pin "1") (pinfunction "1_1") (pintype "passive"))
    )
    (net (code "77") (name "/MUX_DATA2") (class "Default")
      (node (ref "R608") (pin "1") (pinfunction "1_1") (pintype "passive"))
    )
    (net (code "78") (name "/RXTXH_N") (class "Default")
      (node (ref "C608") (pin "1") (pinfunction "1_1") (pintype "passive"))
      (node (ref "D605") (pin "1") (pinfunction "C_1") (pintype "passive"))
      (node (ref "T600") (pin "12") (pintype "passive"))
      (node (ref "TPL_H_N") (pin "1") (pinfunction "1_1") (pintype "passive"))
      (node (ref "U600") (pin "48") (pinfunction "SCLK_RXTXHN_48") (pintype "bidirectional"))
    )
    (net (code "79") (name "/RXTXH_P") (class "Default")
      (node (ref "C602") (pin "2") (pinfunction "2_2") (pintype "passive"))
      (node (ref "D604") (pin "1") (pinfunction "C_1") (pintype "passive"))
      (node (ref "T600") (pin "10") (pintype "passive"))
      (node (ref "TPL_H_P") (pin "1") (pinfunction "1_1") (pintype "passive"))
      (node (ref "U600") (pin "47") (pinfunction "MOSI_RXTXHP_47") (pintype "bidirectional"))
    )
    (net (code "80") (name "/RXTXL_N") (class "Default")
      (node (ref "C612") (pin "1") (pinfunction "1_1") (pintype "passive"))
      (node (ref "D607") (pin "1") (pinfunction "C_1") (pintype "passive"))
      (node (ref "T601") (pin "12") (pintype "passive"))
      (node (ref "TPL_L_N") (pin "1") (pinfunction "1_1") (pintype "passive"))
      (node (ref "U600") (pin "45") (pinfunction "CSN_RXTXLN_45") (pintype "bidirectional"))
    )
    (net (code "81") (name "/RXTXL_P") (class "Default")
      (node (ref "C609") (pin "2") (pinfunction "2_2") (pintype "passive"))
      (node (ref "D606") (pin "1") (pinfunction "C_1") (pintype "passive"))
      (node (ref "T601") (pin "10") (pintype "passive"))
      (node (ref "TPL_L_P") (pin "1") (pinfunction "1_1") (pintype "passive"))
      (node (ref "U600") (pin "46") (pinfunction "RXTXLP_46") (pintype "bidirectional"))
    )
    (net (code "82") (name "/SCL") (class "Default")
      (node (ref "R615") (pin "1") (pinfunction "1_1") (pintype "passive"))
      (node (ref "R616") (pin "1") (pinfunction "1_1") (pintype "passive"))
    )
    (net (code "83") (name "/SDA") (class "Default")
      (node (ref "R617") (pin "1") (pinfunction "1_1") (pintype "passive"))
      (node (ref "R620") (pin "1") (pinfunction "1_1") (pintype "passive"))
    )
    (net (code "86") (name "/T_FILT0") (class "Default")
      (node (ref "R629") (pin "1") (pinfunction "1_1") (pintype "passive"))
    )
    (net (code "87") (name "/T_FILT1") (class "Default")
      (node (ref "R630") (pin "1") (pinfunction "1_1") (pintype "passive"))
    )
    (net (code "88") (name "/T_FILT2") (class "Default")
      (node (ref "R631") (pin "1") (pinfunction "1_1") (pintype "passive"))
    )
    (net (code "89") (name "/T_FILT3") (class "Default")
      (node (ref "R633") (pin "1") (pinfunction "1_1") (pintype "passive"))
    )
    (net (code "90") (name "/T_FILT4") (class "Default")
      (node (ref "R635") (pin "1") (pinfunction "1_1") (pintype "passive"))
    )
    (net (code "91") (name "/T_FILT5") (class "Default")
      (node (ref "R636") (pin "1") (pinfunction "1_1") (pintype "passive"))
    )
    (net (code "92") (name "/T_FILT6") (class "Default")
      (node (ref "R639") (pin "1") (pinfunction "1_1") (pintype "passive"))
    )
    (net (code "93") (name "/T_FILT7") (class "Default")
      (node (ref "R640") (pin "1") (pinfunction "1_1") (pintype "passive"))
    )
    (net (code "95") (name "/Vdd2_unused") (class "Default")
      (node (ref "U601") (pin "10") (pinfunction "VDD2_10") (pintype "power_in+no_connect"))
    )
    (net (code "96") (name "/Vout_unused") (class "Default")
      (node (ref "U601") (pin "9") (pinfunction "VOUT2_9") (pintype "output+no_connect"))
    )
    (net (code "97") (name "GND") (class "Default")
      (node (ref "C600") (pin "1") (pinfunction "1_1") (pintype "passive"))
      (node (ref "C601") (pin "1") (pinfunction "1_1") (pintype "passive"))
      (node (ref "C602") (pin "1") (pinfunction "1_1") (pintype "passive"))
      (node (ref "C603") (pin "1") (pinfunction "1_1") (pintype "passive"))
      (node (ref "C604") (pin "1") (pinfunction "1_1") (pintype "passive"))
      (node (ref "C605") (pin "1") (pinfunction "1_1") (pintype "passive"))
      (node (ref "C606") (pin "1") (pinfunction "1_1") (pintype "passive"))
      (node (ref "C607") (pin "1") (pinfunction "1_1") (pintype "passive"))
      (node (ref "C608") (pin "2") (pinfunction "2_2") (pintype "passive"))
      (node (ref "C609") (pin "1") (pinfunction "1_1") (pintype "passive"))
      (node (ref "C610") (pin "1") (pinfunction "1_1") (pintype "passive"))
      (node (ref "C611") (pin "1") (pinfunction "1_1") (pintype "passive"))
      (node (ref "C612") (pin "2") (pinfunction "2_2") (pintype "passive"))
      (node (ref "C613") (pin "1") (pinfunction "1_1") (pintype "passive"))
      (node (ref "C615") (pin "1") (pinfunction "1_1") (pintype "passive"))
      (node (ref "C617") (pin "1") (pinfunction "1_1") (pintype "passive"))
      (node (ref "C618") (pin "1") (pinfunction "1_1") (pintype "passive"))
      (node (ref "D602") (pin "2") (pinfunction "A_2") (pintype "passive"))
      (node (ref "D604") (pin "2") (pinfunction "A_2") (pintype "passive"))
      (node (ref "D605") (pin "2") (pinfunction "A_2") (pintype "passive"))
      (node (ref "D606") (pin "2") (pinfunction "A_2") (pintype "passive"))
      (node (ref "D607") (pin "2") (pinfunction "A_2") (pintype "passive"))
      (node (ref "D609") (pin "3") (pintype "passive"))
      (node (ref "GND") (pin "1") (pinfunction "1_1") (pintype "passive"))
      (node (ref "Q601") (pin "S") (pinfunction "S_S") (pintype "passive"))
      (node (ref "Q602") (pin "S") (pinfunction "S_S") (pintype "passive"))
      (node (ref "R604") (pin "1") (pinfunction "1_1") (pintype "passive"))
      (node (ref "R605") (pin "1") (pinfunction "1_1") (pintype "passive"))
      (node (ref "R638") (pin "2") (pinfunction "2_2") (pintype "passive"))
      (node (ref "R643") (pin "2") (pinfunction "2_2") (pintype "passive"))
      (node (ref "U600") (pin "43") (pinfunction "VSSC_43") (pintype "power_in"))
      (node (ref "U600") (pin "58") (pinfunction "VSSD_58") (pintype "power_in"))
      (node (ref "U600") (pin "59") (pinfunction "RESET_59") (pintype "input"))
      (node (ref "U600") (pin "62") (pinfunction "VSSA_62") (pintype "power_in"))
      (node (ref "U600") (pin "63") (pinfunction "AINX_GND_63") (pintype "power_in"))
      (node (ref "U600") (pin "64") (pinfunction "GNDSUB_64") (pintype "power_in"))
      (node (ref "U600") (pin "65") (pinfunction "GNDFLAG_65") (pintype "power_in"))
      (node (ref "U601") (pin "3") (pinfunction "GND1_3") (pintype "power_in"))
    )
    (net (code "98") (name "Net-(C607-Pad2)") (class "Default")
      (node (ref "C607") (pin "2") (pinfunction "2_2") (pintype "passive"))
      (node (ref "R611") (pin "1") (pinfunction "1_1") (pintype "passive"))
    )
    (net (code "99") (name "Net-(C610-Pad2)") (class "Default")
      (node (ref "C610") (pin "2") (pinfunction "2_2") (pintype "passive"))
      (node (ref "R621") (pin "1") (pinfunction "1_1") (pintype "passive"))
    )
    (net (code "100") (name "Net-(C614-Pad1)") (class "Default")
      (node (ref "C614") (pin "1") (pinfunction "1_1") (pintype "passive"))
      (node (ref "R632") (pin "2") (pinfunction "2_2") (pintype "passive"))
    )
    (net (code "101") (name "Net-(C614-Pad2)") (class "Default")
      (node (ref "C614") (pin "2") (pinfunction "2_2") (pintype "passive"))
      (node (ref "R628") (pin "2") (pinfunction "2_2") (pintype "passive"))
    )
    (net (code "102") (name "Net-(C615-Pad2)") (class "Default")
      (node (ref "C615") (pin "2") (pinfunction "2_2") (pintype "passive"))
      (node (ref "Q601") (pin "G") (pinfunction "G_G") (pintype "passive"))
      (node (ref "R634") (pin "2") (pinfunction "2_2") (pintype "passive"))
      (node (ref "R638") (pin "1") (pinfunction "1_1") (pintype "passive"))
    )
    (net (code "103") (name "Net-(D608-K)") (class "Default")
      (node (ref "D608") (pin "1") (pinfunction "K_1") (pintype "passive"))
      (node (ref "D609") (pin "2") (pintype "passive"))
      (node (ref "R628") (pin "1") (pinfunction "1_1") (pintype "passive"))
    )
    (net (code "104") (name "Net-(D609-Pad1)") (class "Default")
      (node (ref "D609") (pin "1") (pintype "passive"))
      (node (ref "Q601") (pin "D") (pinfunction "D_D") (pintype "passive"))
      (node (ref "R632") (pin "1") (pinfunction "1_1") (pintype "passive"))
    )
    (net (code "105") (name "Net-(LD600-A)") (class "Default")
      (node (ref "LD600") (pin "2") (pinfunction "A_2") (pintype "passive"))
      (node (ref "R602") (pin "1") (pinfunction "1_1") (pintype "passive"))
    )
    (net (code "106") (name "Net-(LD600-C)") (class "Default")
      (node (ref "LD600") (pin "1") (pinfunction "C_1") (pintype "passive"))
      (node (ref "R604") (pin "2") (pinfunction "2_2") (pintype "passive"))
    )
    (net (code "107") (name "Net-(LD601-A)") (class "Default")
      (node (ref "LD601") (pin "2") (pinfunction "A_2") (pintype "passive"))
      (node (ref "R603") (pin "1") (pinfunction "1_1") (pintype "passive"))
    )
    (net (code "108") (name "Net-(LD601-C)") (class "Default")
      (node (ref "LD601") (pin "1") (pinfunction "C_1") (pintype "passive"))
      (node (ref "R605") (pin "2") (pinfunction "2_2") (pintype "passive"))
    )
    (net (code "109") (name "Net-(R610-Pad1)") (class "Default")
      (node (ref "R610") (pin "1") (pinfunction "1_1") (pintype "passive"))
      (node (ref "T600") (pin "3") (pintype "passive"))
    )
    (net (code "110") (name "Net-(R611-Pad2)") (class "Default")
      (node (ref "R611") (pin "2") (pinfunction "2_2") (pintype "passive"))
      (node (ref "T600") (pin "11") (pintype "passive"))
    )
    (net (code "111") (name "Net-(R612-Pad1)") (class "Default")
      (node (ref "R612") (pin "1") (pinfunction "1_1") (pintype "passive"))
      (node (ref "T600") (pin "1") (pintype "passive"))
    )
    (net (code "112") (name "Net-(R619-Pad1)") (class "Default")
      (node (ref "R619") (pin "1") (pinfunction "1_1") (pintype "passive"))
      (node (ref "T601") (pin "3") (pintype "passive"))
    )
    (net (code "113") (name "Net-(R621-Pad2)") (class "Default")
      (node (ref "R621") (pin "2") (pinfunction "2_2") (pintype "passive"))
      (node (ref "T601") (pin "11") (pintype "passive"))
    )
    (net (code "114") (name "Net-(R622-Pad1)") (class "Default")
      (node (ref "R622") (pin "1") (pinfunction "1_1") (pintype "passive"))
      (node (ref "T601") (pin "1") (pintype "passive"))
    )
    (net (code "115") (name "Net-(U601-AN1)") (class "Default")
      (node (ref "C616") (pin "1") (pinfunction "1_1") (pintype "passive"))
      (node (ref "D610") (pin "1") (pintype "passive"))
      (node (ref "D610") (pin "2") (pintype "passive"))
      (node (ref "U601") (pin "11") (pinfunction "AN1_11") (pintype "input"))
    )
    (net (code "116") (name "Net-(U601-CA1)") (class "Default")
      (node (ref "C616") (pin "2") (pinfunction "2_2") (pintype "passive"))
      (node (ref "D610") (pin "3") (pintype "passive"))
      (node (ref "U601") (pin "12") (pinfunction "CA1_12") (pintype "passive"))
    )
    (net (code "117") (name "VAUX") (class "Default")
      (node (ref "C603") (pin "2") (pinfunction "2_2") (pintype "passive"))
      (node (ref "C604") (pin "2") (pinfunction "2_2") (pintype "passive"))
      (node (ref "C605") (pin "2") (pinfunction "2_2") (pintype "passive"))
      (node (ref "C606") (pin "2") (pinfunction "2_2") (pintype "passive"))
      (node (ref "R603") (pin "2") (pinfunction "2_2") (pintype "passive"))
      (node (ref "U600") (pin "60") (pinfunction "VAUX_60") (pintype "power_in"))
      (node (ref "Vaux") (pin "1") (pinfunction "1_1") (pintype "passive"))
    )
    (net (code "118") (name "VBAT") (class "Default")
      (node (ref "C601") (pin "2") (pinfunction "2_2") (pintype "passive"))
      (node (ref "R600") (pin "1") (pinfunction "1_1") (pintype "passive"))
      (node (ref "U600") (pin "1") (pinfunction "VBAT_1") (pintype "power_in"))
      (node (ref "Vbat") (pin "1") (pinfunction "1_1") (pintype "passive"))
    )
    (net (code "119") (name "VBAT_con") (class "Default")
      (node (ref "D600") (pin "2") (pinfunction "A_2") (pintype "passive"))
    )
    (net (code "120") (name "VBAT_con_ext") (class "Default")
      (node (ref "C600") (pin "2") (pinfunction "2_2") (pintype "passive"))
      (node (ref "D600") (pin "1") (pinfunction "K_1") (pintype "passive"))
      (node (ref "D601") (pin "1") (pinfunction "K_1") (pintype "passive"))
      (node (ref "D602") (pin "1") (pinfunction "C_1") (pintype "passive"))
      (node (ref "D603") (pin "1") (pinfunction "K_1") (pintype "passive"))
      (node (ref "Q600") (pin "2") (pinfunction "C_2") (pintype "passive"))
      (node (ref "Q600") (pin "4") (pinfunction "C_4") (pintype "passive"))
      (node (ref "R600") (pin "2") (pinfunction "2_2") (pintype "passive"))
      (node (ref "Vbat_con_ext") (pin "1") (pinfunction "1_1") (pintype "passive"))
    )
    (net (code "121") (name "VBAT_ext") (class "Default")
      (node (ref "D601") (pin "2") (pinfunction "A_2") (pintype "passive"))
    )
    (net (code "122") (name "VDDA") (class "Default")
      (node (ref "C613") (pin "2") (pinfunction "2_2") (pintype "passive"))
      (node (ref "U600") (pin "61") (pinfunction "VDDA_61") (pintype "power_in"))
    )
    (net (code "123") (name "VDDC") (class "Default")
      (node (ref "C611") (pin "2") (pinfunction "2_2") (pintype "passive"))
      (node (ref "C617") (pin "2") (pinfunction "2_2") (pintype "passive"))
      (node (ref "D608") (pin "2") (pinfunction "A_2") (pintype "passive"))
      (node (ref "R601") (pin "1") (pinfunction "1_1") (pintype "passive"))
      (node (ref "R602") (pin "2") (pinfunction "2_2") (pintype "passive"))
      (node (ref "R618") (pin "1") (pinfunction "1_1") (pintype "passive"))
      (node (ref "R627") (pin "1") (pinfunction "1_1") (pintype "passive"))
      (node (ref "R637") (pin "2") (pinfunction "2_2") (pintype "passive"))
      (node (ref "R641") (pin "1") (pinfunction "1_1") (pintype "passive"))
      (node (ref "U600") (pin "40") (pinfunction "VDDC_40") (pintype "power_in"))
      (node (ref "U601") (pin "1") (pinfunction "VDD1_1") (pintype "power_in"))
      (node (ref "Vddc") (pin "1") (pinfunction "1_1") (pintype "passive"))
    )
    (net (code "124") (name "VDDIO") (class "Default")
      (node (ref "R616") (pin "2") (pinfunction "2_2") (pintype "passive"))
      (node (ref "R617") (pin "2") (pinfunction "2_2") (pintype "passive"))
      (node (ref "R637") (pin "1") (pinfunction "1_1") (pintype "passive"))
      (node (ref "U600") (pin "39") (pinfunction "VDDIO_39") (pintype "power_in"))
    )
    (net (code "125") (name "VMODULE") (class "Default")
      (node (ref "U600") (pin "17") (pinfunction "VMODULE_17") (pintype "input"))
      (node (ref "Vmodule") (pin "1") (pinfunction "1_1") (pintype "passive"))
    )
    (net (code "126") (name "unconnected-(R610-Pad2)") (class "Default")
      (node (ref "R610") (pin "2") (pinfunction "2_2") (pintype "passive"))
    )
    (net (code "127") (name "unconnected-(R612-Pad2)") (class "Default")
      (node (ref "R612") (pin "2") (pinfunction "2_2") (pintype "passive"))
    )
    (net (code "128") (name "unconnected-(R619-Pad2)") (class "Default")
      (node (ref "R619") (pin "2") (pinfunction "2_2") (pintype "passive"))
    )
    (net (code "129") (name "unconnected-(R622-Pad2)") (class "Default")
      (node (ref "R622") (pin "2") (pinfunction "2_2") (pintype "passive"))
    )
    (net (code "130") (name "unconnected-(T600-Pad2)") (class "Default")
      (node (ref "T600") (pin "2") (pintype "passive+no_connect"))
    )
    (net (code "131") (name "unconnected-(T600-Pad4)") (class "Default")
      (node (ref "T600") (pin "4") (pintype "passive+no_connect"))
    )
    (net (code "132") (name "unconnected-(T600-Pad5)") (class "Default")
      (node (ref "T600") (pin "5") (pintype "passive+no_connect"))
    )
    (net (code "133") (name "unconnected-(T600-Pad6)") (class "Default")
      (node (ref "T600") (pin "6") (pintype "passive+no_connect"))
    )
    (net (code "134") (name "unconnected-(T600-Pad7)") (class "Default")
      (node (ref "T600") (pin "7") (pintype "passive+no_connect"))
    )
    (net (code "135") (name "unconnected-(T600-Pad8)") (class "Default")
      (node (ref "T600") (pin "8") (pintype "passive+no_connect"))
    )
    (net (code "136") (name "unconnected-(T600-Pad9)") (class "Default")
      (node (ref "T600") (pin "9") (pintype "passive+no_connect"))
    )
    (net (code "137") (name "unconnected-(T601-Pad2)") (class "Default")
      (node (ref "T601") (pin "2") (pintype "passive+no_connect"))
    )
    (net (code "138") (name "unconnected-(T601-Pad4)") (class "Default")
      (node (ref "T601") (pin "4") (pintype "passive+no_connect"))
    )
    (net (code "139") (name "unconnected-(T601-Pad5)") (class "Default")
      (node (ref "T601") (pin "5") (pintype "passive+no_connect"))
    )
    (net (code "140") (name "unconnected-(T601-Pad6)") (class "Default")
      (node (ref "T601") (pin "6") (pintype "passive+no_connect"))
    )
    (net (code "141") (name "unconnected-(T601-Pad7)") (class "Default")
      (node (ref "T601") (pin "7") (pintype "passive+no_connect"))
    )
    (net (code "142") (name "unconnected-(T601-Pad8)") (class "Default")
      (node (ref "T601") (pin "8") (pintype "passive+no_connect"))
    )
    (net (code "143") (name "unconnected-(T601-Pad9)") (class "Default")
      (node (ref "T601") (pin "9") (pintype "passive+no_connect"))
    )
    (net (code "144") (name "unconnected-(U600-MISO-Pad44)") (class "Default")
      (node (ref "U600") (pin "44") (pinfunction "MISO_44") (pintype "output+no_connect"))
    )
    (net (code "145") (name "unconnected-(U601-AN2-Pad4)") (class "Default")
      (node (ref "U601") (pin "4") (pinfunction "AN2_4") (pintype "input+no_connect"))
    )
    (net (code "146") (name "unconnected-(U601-CA2-Pad5)") (class "Default")
      (node (ref "U601") (pin "5") (pinfunction "CA2_5") (pintype "passive+no_connect"))
    )
    (net (code "147") (name "unconnected-(U601-CA2-Pad6)") (class "Default")
      (node (ref "U601") (pin "6") (pinfunction "CA2_6") (pintype "passive+no_connect"))
    )
  )
)
